# Busswitch.net
KiCad netlist of a schematic drawn in Altium Designer
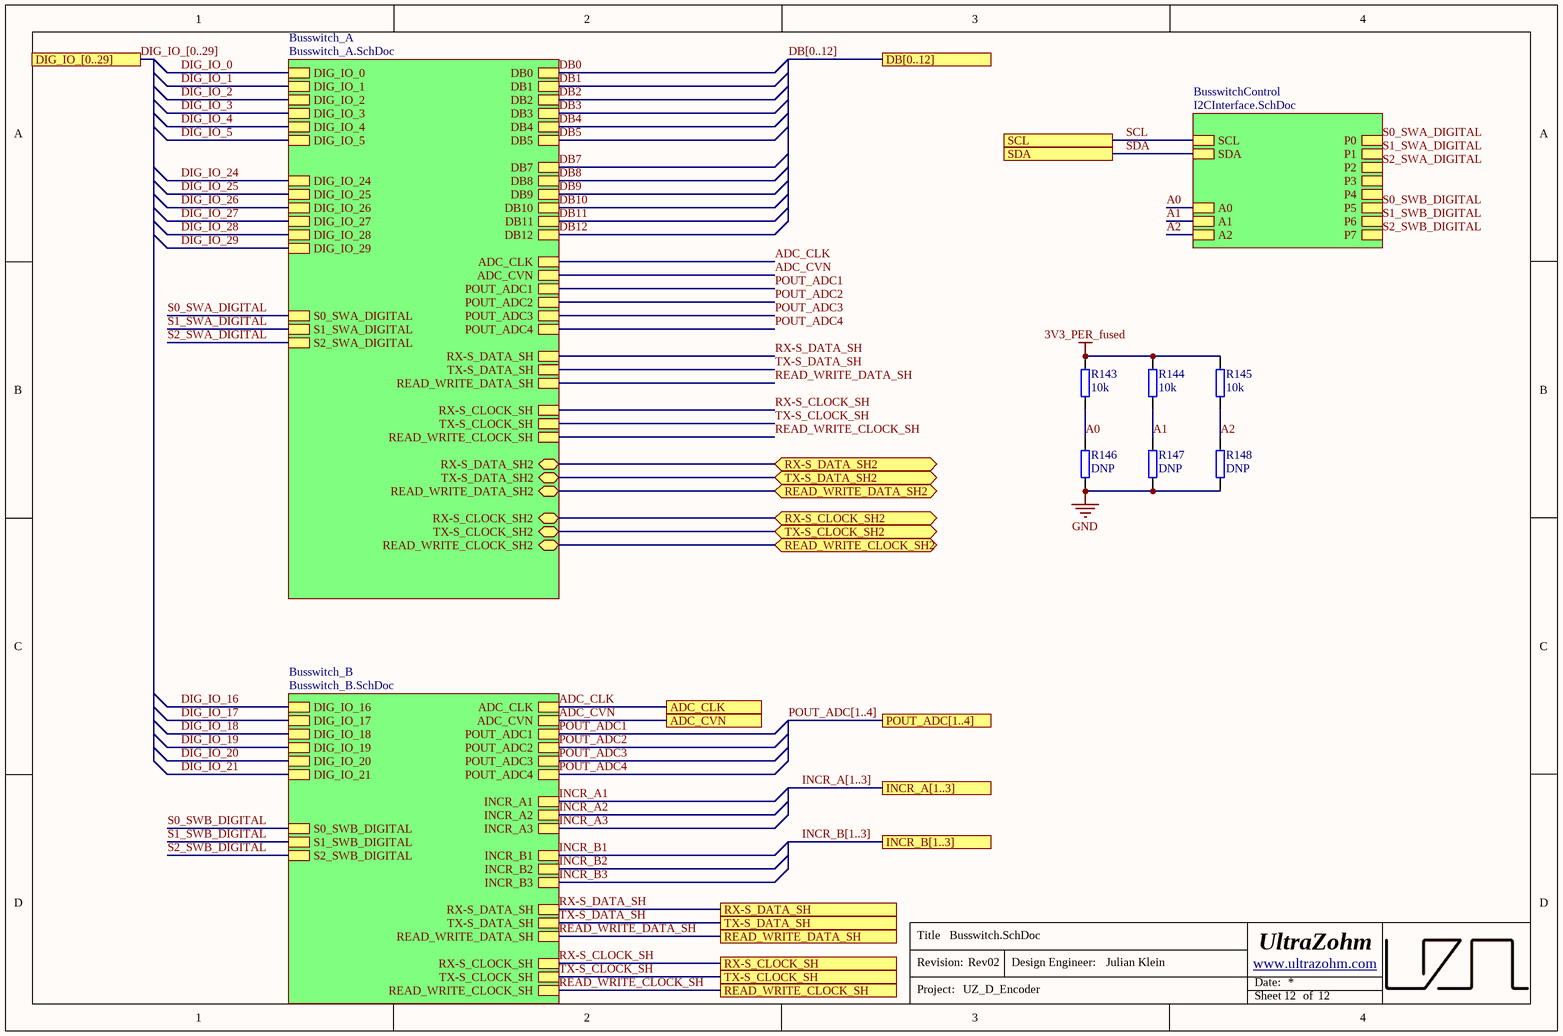
[diagram p0: Busswitch.SchDoc]

(export (version "E")
  (design (tool "Eeschema 10.0.6"))
  (components
    (comp (ref "R143")
      (value "10k")
      (footprint "RESC1608X06N")
      (fields (field (name "MF") "Vishay") (field (name "MPN") "CRCW06030000Z0EAC"))
      (libsource (lib "UltraZohm_ADC") (part "R_0603"))
    )
    (comp (ref "R144")
      (value "10k")
      (footprint "RESC1608X06N")
      (fields (field (name "MF") "Vishay") (field (name "MPN") "CRCW06030000Z0EAC"))
      (libsource (lib "UltraZohm_ADC") (part "R_0603"))
    )
    (comp (ref "R145")
      (value "10k")
      (footprint "RESC1608X06N")
      (fields (field (name "MF") "Vishay") (field (name "MPN") "CRCW06030000Z0EAC"))
      (libsource (lib "UltraZohm_ADC") (part "R_0603"))
    )
    (comp (ref "R146")
      (value "DNP")
      (footprint "RESC1608X06N")
      (fields (field (name "MF") "Vishay") (field (name "MPN") "CRCW06030000Z0EAC"))
      (libsource (lib "UltraZohm_ADC") (part "R_0603"))
    )
    (comp (ref "R147")
      (value "DNP")
      (footprint "RESC1608X06N")
      (fields (field (name "MF") "Vishay") (field (name "MPN") "CRCW06030000Z0EAC"))
      (libsource (lib "UltraZohm_ADC") (part "R_0603"))
    )
    (comp (ref "R148")
      (value "DNP")
      (footprint "RESC1608X06N")
      (fields (field (name "MF") "Vishay") (field (name "MPN") "CRCW06030000Z0EAC"))
      (libsource (lib "UltraZohm_ADC") (part "R_0603"))
    )
  )
  (nets
    (net (code "14") (name "/A0") (class "Default")
      (node (ref "R143") (pin "2") (pintype "passive"))
      (node (ref "R146") (pin "1") (pintype "passive"))
    )
    (net (code "15") (name "/A1") (class "Default")
      (node (ref "R144") (pin "2") (pintype "passive"))
      (node (ref "R147") (pin "1") (pintype "passive"))
    )
    (net (code "16") (name "/A2") (class "Default")
      (node (ref "R145") (pin "2") (pintype "passive"))
      (node (ref "R148") (pin "1") (pintype "passive"))
    )
    (net (code "86") (name "3V3_PER_fused") (class "Default")
      (node (ref "R143") (pin "1") (pintype "passive"))
      (node (ref "R144") (pin "1") (pintype "passive"))
      (node (ref "R145") (pin "1") (pintype "passive"))
    )
    (net (code "87") (name "GND") (class "Default")
      (node (ref "R146") (pin "2") (pintype "passive"))
      (node (ref "R147") (pin "2") (pintype "passive"))
      (node (ref "R148") (pin "2") (pintype "passive"))
    )
  )
)
